# ProPrj_5V2A_2026-09-02.net
KiCad netlist of a schematic drawn in EasyEDA Pro
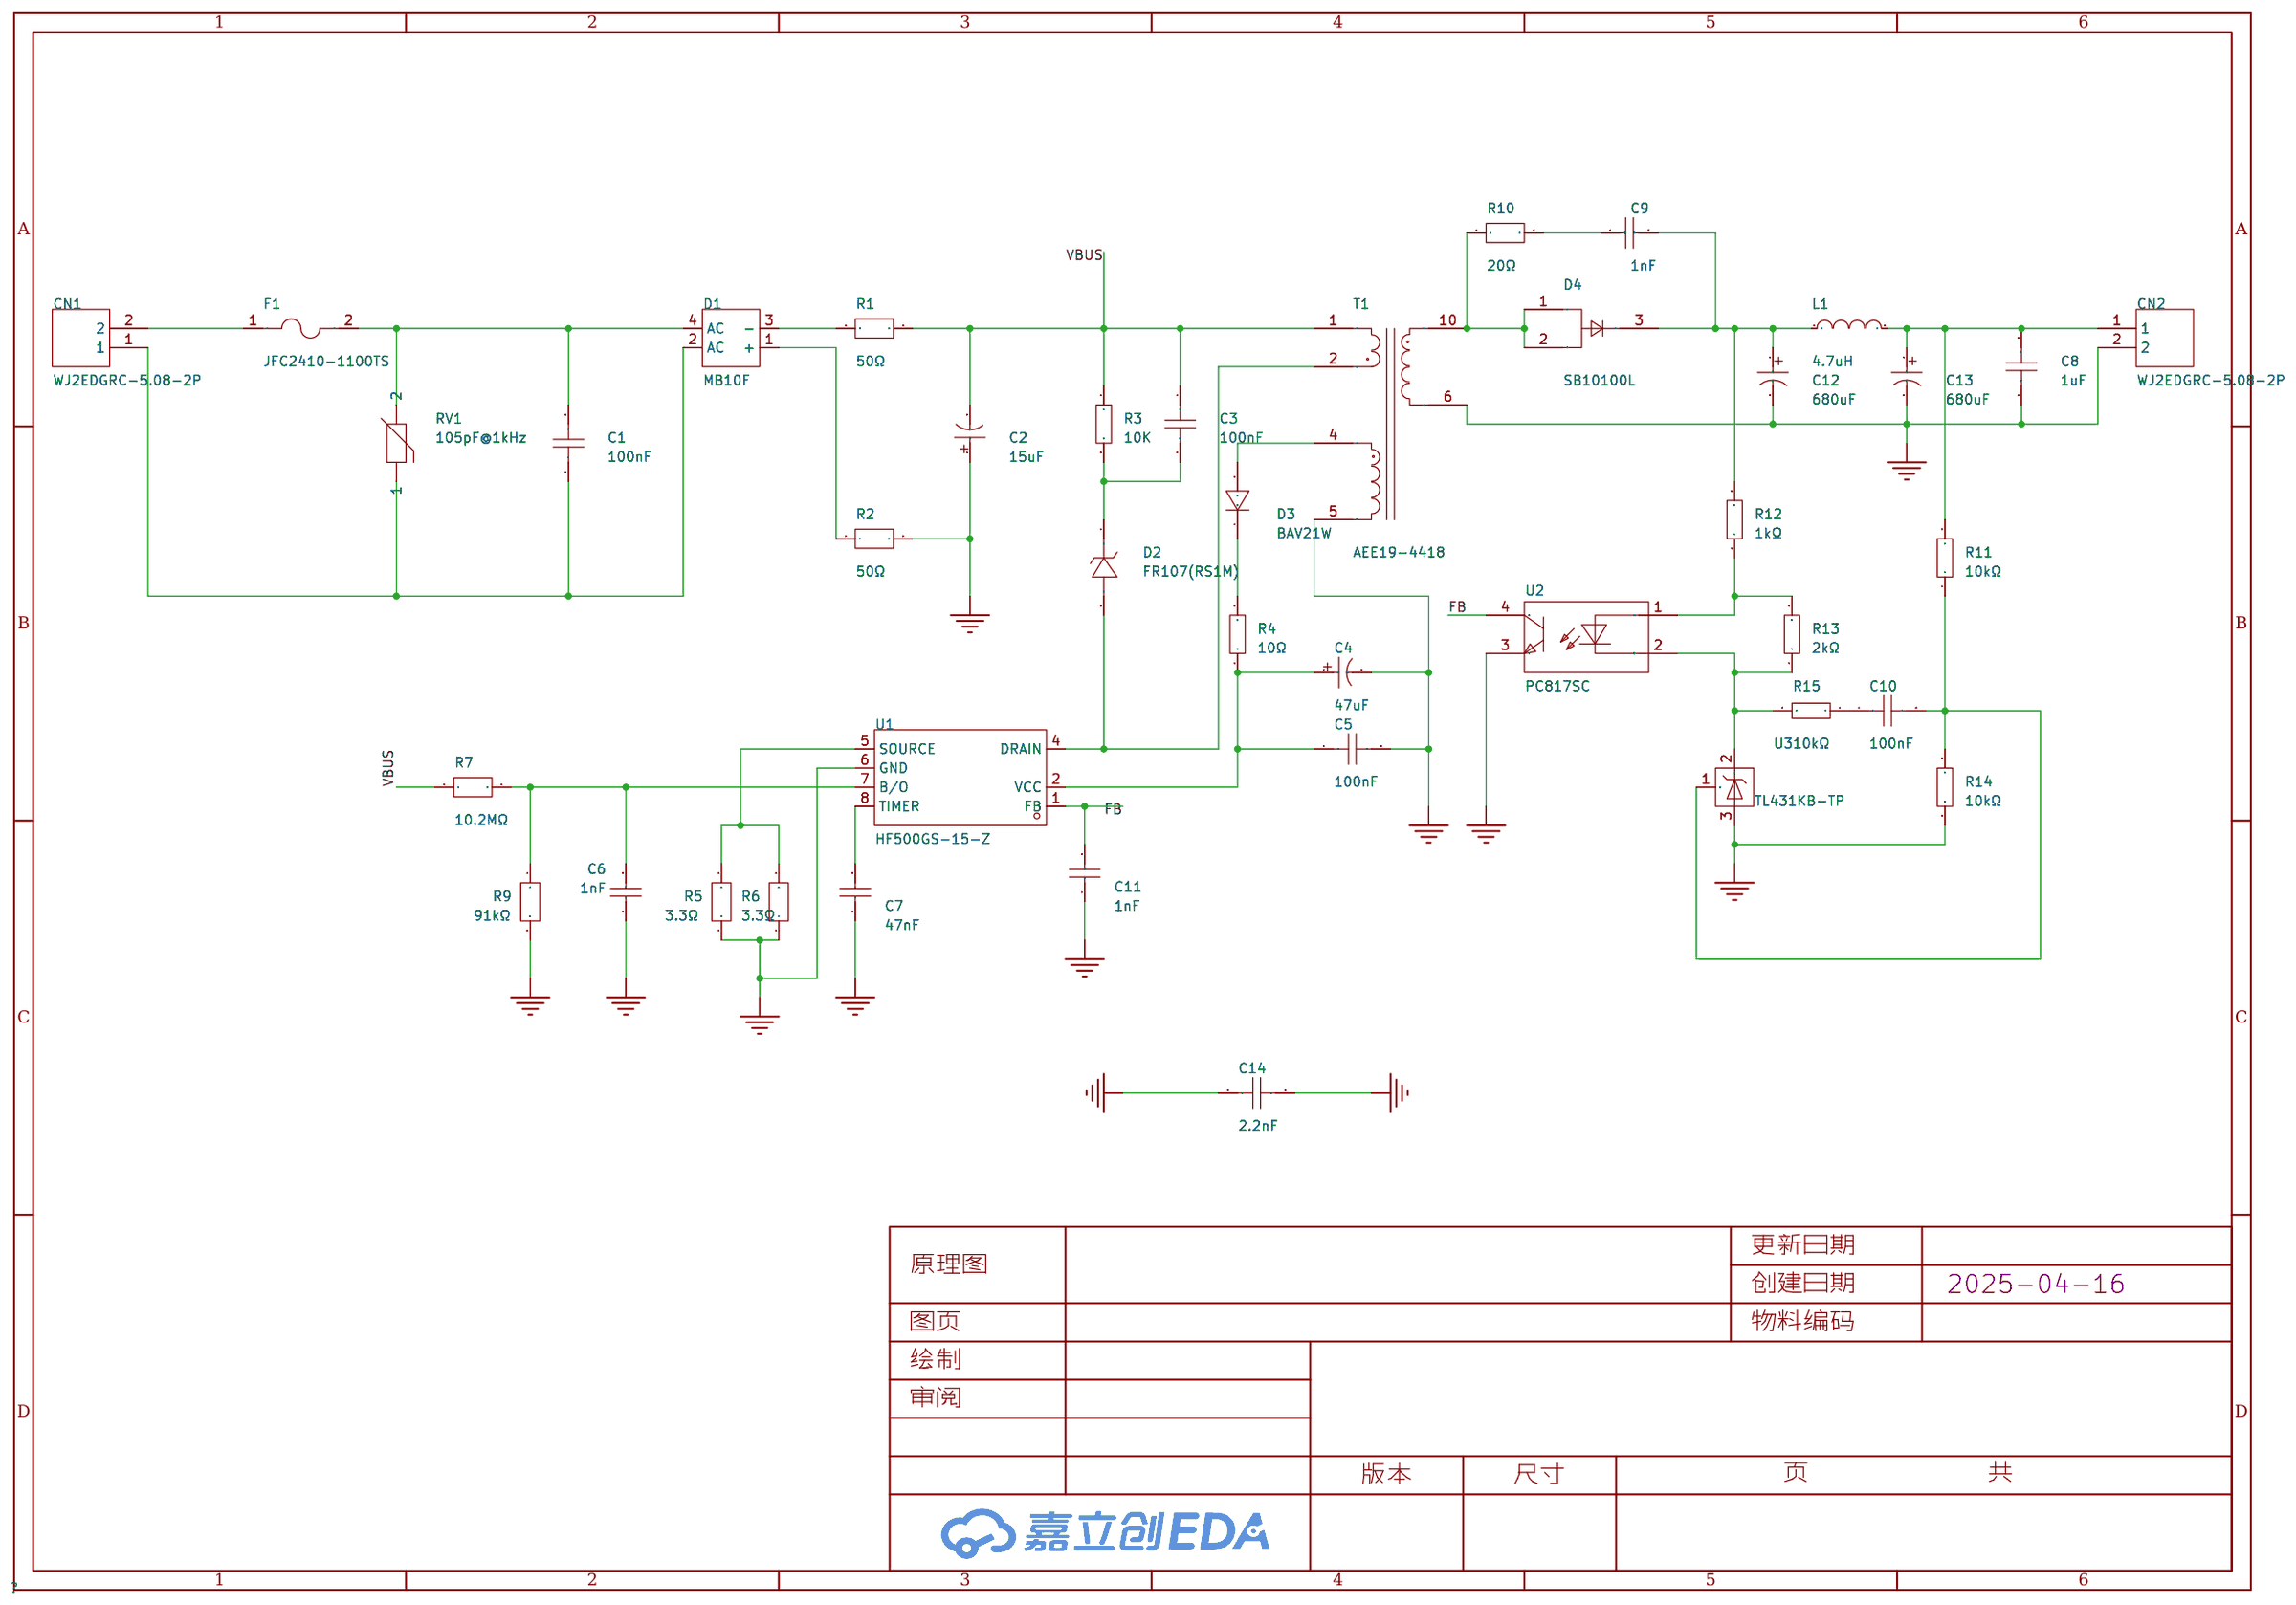
[diagram p0: schematic sheet]

(export (version "E")
  (design (tool "Eeschema 10.0.6"))
  (components
    (comp (ref "C1")
      (value "100nF")
      (footprint "easyedapro:CAP-TH_L13.0-W6.0-P10.00-D0.6")
      (description "容值:100nF;精度:±10%;工作电压(AC):275V；310V；305V;防护等级:X2;")
      (fields
        (field (name "Manufacturer Part") "MPX104K31C3KN15600")
        (field (name "Manufacturer") "KNSCHA(科尼盛)")
      )
      (libsource (lib "easyedapro") (part "MPX104K31C3KN15600"))
    )
    (comp (ref "C2")
      (value "15uF")
      (footprint "easyedapro:CAP-TH_BD10.0-P5.00-D1.0-FD")
      (description "容值:15uF;精度:±20%;额定电压:400V;纹波电流:-;等效串联电阻(ESR):-;")
      (fields
        (field (name "Manufacturer Part") "KM156M400G17RR0VH2FP0")
        (field (name "Manufacturer") "CX(承兴)")
      )
      (libsource (lib "easyedapro") (part "15UF/400V"))
    )
    (comp (ref "C3")
      (value "100nF")
      (footprint "easyedapro:C0603")
      (libsource (lib "easyedapro") (part "CapAcitance"))
    )
    (comp (ref "C4")
      (value "47uF")
      (footprint "easyedapro:CAP-TH_BD6.3-P2.50-D1.0-FD")
      (description "容值:47uF;精度:±20%;额定电压:50V;")
      (fields
        (field (name "Manufacturer Part") "KM476M050E11RR0VH2FP0")
        (field (name "Manufacturer") "CX(承兴)")
      )
      (libsource (lib "easyedapro") (part "47uF 50V 6.3*11_C45101"))
    )
    (comp (ref "C5")
      (value "100nF")
      (footprint "easyedapro:C0603")
      (description "容值:100nF;精度:±10%;额定电压:50V;温度系数:X7R;")
      (fields
        (field (name "Manufacturer Part") "CGA0603X7R104K500JT")
        (field (name "Manufacturer") "HRE(芯声)")
      )
      (libsource (lib "easyedapro") (part "CGA0603X7R104K500JT"))
    )
    (comp (ref "C6")
      (value "1nF")
      (footprint "easyedapro:C1206")
      (description "容值:1nF;精度:±10%;额定电压:2kV;温度系数:X7R;")
      (fields (field (name "Manufacturer Part") "1206B102K202NT") (field (name "Manufacturer") "FH(风华)"))
      (libsource (lib "easyedapro") (part "1206B102K202NT"))
    )
    (comp (ref "C7")
      (value "47nF")
      (footprint "easyedapro:C0603")
      (description "容值:47nF;精度:±10%;额定电压:50V;材质(温度系数):X7R;")
      (fields
        (field (name "Manufacturer Part") "CL10B473KB8NNNC")
        (field (name "Manufacturer") "SAMSUNG(三星)")
      )
      (libsource (lib "easyedapro") (part "CL10B473KB8NNNC"))
    )
    (comp (ref "C8")
      (value "1uF")
      (footprint "easyedapro:C0402")
      (description "容值:1uF;精度:±10%;额定电压:25V;材质(温度系数):X5R;")
      (fields
        (field (name "Manufacturer Part") "CL05A105KA5NQNC")
        (field (name "Manufacturer") "SAMSUNG(三星)")
      )
      (libsource (lib "easyedapro") (part "CL05A105KA5NQNC"))
    )
    (comp (ref "C9")
      (value "1nF")
      (footprint "easyedapro:C0603")
      (description "容值:1nF;精度:±10%;额定电压:50V;材质(温度系数):X7R;")
      (fields
        (field (name "Manufacturer Part") "CC0603KRX7R9BB102")
        (field (name "Manufacturer") "YAGEO(国巨)")
      )
      (libsource (lib "easyedapro") (part "CC0603KRX7R9BB102"))
    )
    (comp (ref "C10")
      (value "100nF")
      (footprint "easyedapro:C0603")
      (description "容值:100nF;精度:±10%;额定电压:50V;温度系数:X7R;")
      (fields
        (field (name "Manufacturer Part") "CGA0603X7R104K500JT")
        (field (name "Manufacturer") "HRE(芯声)")
      )
      (libsource (lib "easyedapro") (part "CGA0603X7R104K500JT"))
    )
    (comp (ref "C11")
      (value "1nF")
      (footprint "easyedapro:C0603")
      (description "容值:1nF;精度:±10%;额定电压:50V;材质(温度系数):X7R;")
      (fields
        (field (name "Manufacturer Part") "CL10B102KB8NNNC")
        (field (name "Manufacturer") "SAMSUNG(三星)")
      )
      (libsource (lib "easyedapro") (part "CL10B102KB8NNNC"))
    )
    (comp (ref "C12")
      (value "680uF")
      (footprint "easyedapro:CAP-TH_BD8.0-P3.50-D0.6-FD")
      (description "容值:680uF;精度:±20%;额定电压:16V;纹波电流:5.1A@100kHz;等效串联电阻(ESR):11mΩ@100kHz;类型:-;")
      (fields
        (field (name "Manufacturer Part") "ULR687M1CF1ARR")
        (field (name "Manufacturer") "MAN YUE(万裕科技)")
      )
      (libsource (lib "easyedapro") (part "ULR687M1CF1ARRX0CR"))
    )
    (comp (ref "C13")
      (value "680uF")
      (footprint "easyedapro:CAP-TH_BD8.0-P3.50-D0.6-FD")
      (description "容值:680uF;精度:±20%;额定电压:16V;纹波电流:5.1A@100kHz;等效串联电阻(ESR):11mΩ@100kHz;类型:-;")
      (fields
        (field (name "Manufacturer Part") "ULR687M1CF1ARR")
        (field (name "Manufacturer") "MAN YUE(万裕科技)")
      )
      (libsource (lib "easyedapro") (part "ULR687M1CF1ARRX0CR"))
    )
    (comp (ref "C14")
      (value "2.2nF")
      (footprint "easyedapro:CAP-TH_L10.0-W4.5-P10.00-D0.6-S4.0")
      (description "容值:2.2nF;精度:±20%;工作电压(AC):400V;防护等级:Y1;")
      (fields
        (field (name "Manufacturer Part") "AJTF222M2GF0200A082E")
        (field (name "Manufacturer") "KNSCHA(科尼盛)")
      )
      (libsource (lib "easyedapro") (part "AJTF222M2GF0200A082E"))
    )
    (comp (ref "CN1")
      (value "WJ2EDGRC-5.08-2P")
      (footprint "easyedapro:CONN-TH_2P-P5.08_WJ2EDGRC-5.08-2P")
      (fields (field (name "Manufacturer") "KANGNEX(康奈克斯电气)"))
      (libsource (lib "easyedapro") (part "WJ2EDGRC-5.08-2P"))
    )
    (comp (ref "CN2")
      (value "WJ2EDGRC-5.08-2P")
      (footprint "easyedapro:CONN-TH_2P-P5.08_WJ2EDGRC-5.08-2P")
      (fields (field (name "Manufacturer") "KANGNEX(康奈克斯电气)"))
      (libsource (lib "easyedapro") (part "WJ2EDGRC-5.08-2P"))
    )
    (comp (ref "D1")
      (value "MB10F")
      (footprint "easyedapro:MBF_L4.8-W3.9-P2.50-LS6.7-TR")
      (description "正向压降(Vf):1.1V@800mA;直流反向耐压(Vr):1kV;整流电流:800mA;正向浪涌电流(Ifsm):30A;")
      (fields (field (name "Manufacturer") "Hottech(合科泰)"))
      (libsource (lib "easyedapro") (part "MB10FH5G0NP"))
    )
    (comp (ref "D2")
      (value "FR107(RS1M)")
      (footprint "easyedapro:SMA_L4.3-W2.6-LS5.2-RD")
      (description "二极管配置:独立式;正向压降(Vf):1.3V@1A;直流反向耐压(Vr):1kV;整流电流:1A;反向恢复时间(trr):500ns;")
      (fields (field (name "Manufacturer") "KEXIN(科信)"))
      (libsource (lib "easyedapro") (part "FR107(RS1M)"))
    )
    (comp (ref "D3")
      (value "BAV21W")
      (footprint "easyedapro:SOD-123_L2.8-W1.8-LS3.7-RD")
      (description "二极管配置:独立式;正向压降(Vf):1.25V@200mA;直流反向耐压(Vr):200V;整流电流:200mA;反向恢复时间(trr):50ns;")
      (fields (field (name "Manufacturer") "CJ(江苏长电/长晶)"))
      (libsource (lib "easyedapro") (part "BAV21W"))
    )
    (comp (ref "D4")
      (value "SB10100L")
      (footprint "easyedapro:TO-277A_L4.7-W6.1-LS6.6-TR")
      (description "正向压降(Vf):850mV@10A;直流反向耐压(Vr):100V;整流电流:10A;")
      (fields (field (name "Manufacturer") "MDD(辰达半导体)"))
      (libsource (lib "easyedapro") (part "SB10100L"))
    )
    (comp (ref "F1")
      (value "JFC2410-1100TS")
      (footprint "easyedapro:F2410")
      (description "类型:贴片式保险丝;额定电流:1A;额定电压 (AC):250V;额定电压:250V;分断能力:50A;")
      (fields (field (name "Manufacturer") "JDTfuse(集电通)"))
      (libsource (lib "easyedapro") (part "JFC2410-1100TS"))
    )
    (comp (ref "L1")
      (value "4.7uH")
      (footprint "easyedapro:IND-SMD_L7.0-W6.6")
      (description "电感值:4.7uH;精度:±20%;额定电流:6A;饱和电流(Isat):9A;类型:一体成型电感;")
      (fields (field (name "Manufacturer Part") "FXL0630-4R7-M") (field (name "Manufacturer") "cjiang(长江微电)"))
      (libsource (lib "easyedapro") (part "FXL0630-4R7-M"))
    )
    (comp (ref "R1")
      (value "50Ω")
      (footprint "easyedapro:R1206")
      (description "电阻类型:薄膜电阻;阻值:50Ω;精度:±1%;功率:-;温度系数:±10ppm/°C;")
      (fields (field (name "Manufacturer Part") "AR06FTBV0500") (field (name "Manufacturer") "Viking(光颉)"))
      (libsource (lib "easyedapro") (part "AR06FTBV0500"))
    )
    (comp (ref "R2")
      (value "50Ω")
      (footprint "easyedapro:R1206")
      (description "电阻类型:薄膜电阻;阻值:50Ω;精度:±1%;功率:-;温度系数:±10ppm/°C;")
      (fields (field (name "Manufacturer Part") "AR06FTBV0500") (field (name "Manufacturer") "Viking(光颉)"))
      (libsource (lib "easyedapro") (part "AR06FTBV0500"))
    )
    (comp (ref "R3") (value "10K") (footprint "easyedapro:R0603") (libsource (lib "easyedapro") (part "电阻")))
    (comp (ref "R4")
      (value "10Ω")
      (footprint "easyedapro:R0603")
      (description "电阻类型:厚膜电阻;阻值:10Ω;精度:±1%;功率:100mW;最大工作电压:75V;温度系数:±400ppm/°C;")
      (fields
        (field (name "Manufacturer Part") "0603WAF100JT5E")
        (field (name "Manufacturer") "UNI-ROYAL(厚声)")
      )
      (libsource (lib "easyedapro") (part "0603WAF100JT5E"))
    )
    (comp (ref "R5")
      (value "3.3Ω")
      (footprint "easyedapro:R1206")
      (description "电阻类型:厚膜电阻;阻值:3.3Ω;精度:±1%;功率:250mW;最大工作电压:200V;温度系数:±200ppm/°C;")
      (fields (field (name "Manufacturer Part") "FRC1206F3R30TS") (field (name "Manufacturer") "FOJAN(富捷)"))
      (libsource (lib "easyedapro") (part "FRC1206F3R30TS"))
    )
    (comp (ref "R6")
      (value "3.3Ω")
      (footprint "easyedapro:R1206")
      (description "电阻类型:厚膜电阻;阻值:3.3Ω;精度:±1%;功率:250mW;最大工作电压:200V;温度系数:±200ppm/°C;")
      (fields (field (name "Manufacturer Part") "FRC1206F3R30TS") (field (name "Manufacturer") "FOJAN(富捷)"))
      (libsource (lib "easyedapro") (part "FRC1206F3R30TS"))
    )
    (comp (ref "R7")
      (value "10.2MΩ")
      (footprint "easyedapro:R1206")
      (description "电阻类型:厚膜电阻;阻值:10.2MΩ;精度:±1%;功率:250mW;最大工作电压:200V;温度系数:±100ppm/°C;")
      (fields
        (field (name "Manufacturer Part") "1206W4F1025T5E")
        (field (name "Manufacturer") "UNI-ROYAL(厚声)")
      )
      (libsource (lib "easyedapro") (part "1206W4F1025T5E"))
    )
    (comp (ref "R9")
      (value "91kΩ")
      (footprint "easyedapro:R0603")
      (description "电阻类型:厚膜电阻;阻值:91kΩ;精度:±1%;功率:100mW;工作电压:75V;温度系数:±100ppm/°C;")
      (fields (field (name "Manufacturer Part") "FRC0603F9102TS") (field (name "Manufacturer") "FOJAN(富捷)"))
      (libsource (lib "easyedapro") (part "FRC0603F9102TS"))
    )
    (comp (ref "R10")
      (value "20Ω")
      (footprint "easyedapro:R0603")
      (description "电阻类型:厚膜电阻;阻值:20Ω;精度:±1%;功率:100mW;工作电压:75V;温度系数:±100ppm/°C;")
      (fields (field (name "Manufacturer Part") "FRC0603F20R0TS") (field (name "Manufacturer") "FOJAN(富捷)"))
      (libsource (lib "easyedapro") (part "FRC0603F20R0TS"))
    )
    (comp (ref "R11")
      (value "10kΩ")
      (footprint "easyedapro:R0603")
      (description "电阻类型:厚膜电阻;阻值:10kΩ;精度:±1%;功率:100mW;最大工作电压:75V;温度系数:±100ppm/°C;")
      (fields
        (field (name "Manufacturer Part") "0603WAF1002T5E")
        (field (name "Manufacturer") "UNI-ROYAL(厚声)")
      )
      (libsource (lib "easyedapro") (part "0603WAF1002T5E"))
    )
    (comp (ref "R12")
      (value "1kΩ")
      (footprint "easyedapro:R0603")
      (description "电阻类型:厚膜电阻;阻值:1kΩ;精度:±1%;功率:100mW;最大工作电压:75V;温度系数:±100ppm/°C;")
      (fields
        (field (name "Manufacturer Part") "0603WAF1001T5E")
        (field (name "Manufacturer") "UNI-ROYAL(厚声)")
      )
      (libsource (lib "easyedapro") (part "0603WAF1001T5E"))
    )
    (comp (ref "R13")
      (value "2kΩ")
      (footprint "easyedapro:R0603")
      (description "电阻类型:厚膜电阻;阻值:2kΩ;精度:±1%;功率:100mW;最大工作电压:75V;温度系数:±100ppm/°C;")
      (fields
        (field (name "Manufacturer Part") "0603WAF2001T5E")
        (field (name "Manufacturer") "UNI-ROYAL(厚声)")
      )
      (libsource (lib "easyedapro") (part "0603WAF2001T5E"))
    )
    (comp (ref "R14")
      (value "10kΩ")
      (footprint "easyedapro:R0603")
      (description "电阻类型:厚膜电阻;阻值:10kΩ;精度:±1%;功率:100mW;最大工作电压:75V;温度系数:±100ppm/°C;")
      (fields
        (field (name "Manufacturer Part") "0603WAF1002T5E")
        (field (name "Manufacturer") "UNI-ROYAL(厚声)")
      )
      (libsource (lib "easyedapro") (part "0603WAF1002T5E"))
    )
    (comp (ref "R15")
      (value "10kΩ")
      (footprint "easyedapro:R0603")
      (description "电阻类型:厚膜电阻;阻值:10kΩ;精度:±1%;功率:100mW;最大工作电压:75V;温度系数:±100ppm/°C;")
      (fields
        (field (name "Manufacturer Part") "0603WAF1002T5E")
        (field (name "Manufacturer") "UNI-ROYAL(厚声)")
      )
      (libsource (lib "easyedapro") (part "0603WAF1002T5E"))
    )
    (comp (ref "RV1")
      (value "105pF@1kHz")
      (footprint "easyedapro:RES-TH_L9.0-W5.0-P6.00-D0.7-S3.00")
      (description "压敏电压:423V~517V;钳位电压:810V;工作电压:385V;工作电压(AC):300V;")
      (fields (field (name "Manufacturer Part") "07D471K") (field (name "Manufacturer") "COV(德欣)"))
      (libsource (lib "easyedapro") (part "07D471K_C317765"))
    )
    (comp (ref "T1")
      (value "AEE19-4418")
      (footprint "easyedapro:XFMR-TH_9P-L20.5-W16.9-P3.90-D0.7-S13.00_AEE19-4418")
      (description "初级电压:-;")
      (fields (field (name "Manufacturer") "Allied Components International"))
      (libsource (lib "easyedapro") (part "AEE19-4418"))
    )
    (comp (ref "U1")
      (value "HF500GS-15-Z")
      (footprint "easyedapro:SOIC-8_7P-L4.9-W3.9-P1.27-LS6.0-BL-PE3")
      (description "工作电压:12.5V~24V;开关频率:25kHz;晶体管耐压:700V;")
      (fields (field (name "Manufacturer") "MPS(芯源)"))
      (libsource (lib "easyedapro") (part "HF500GS-15-Z"))
    )
    (comp (ref "U2")
      (value "PC817SC")
      (footprint "easyedapro:SMD-4_L4.6-W6.5-P2.54-LS10.2-BL")
      (description "可替代C115502")
      (libsource (lib "easyedapro") (part "PC817S"))
    )
    (comp (ref "U3")
      (value "TL431KB-TP")
      (footprint "easyedapro:SOT-23-3_L2.9-W1.4-P1.91-LS2.6-BR")
      (description "输出类型:可编程;输入电压:-;输出电压:2.495V~36V;输出电流:100mA;精度:±0.4%;")
      (fields (field (name "Manufacturer") "MCC(美微科)"))
      (libsource (lib "easyedapro") (part "TL431KB-TP"))
    )
  )
  (nets
    (net (code "1") (name "/FB") (class "Default")
      (node (ref "C11") (pin "2") (pinfunction "2_2") (pintype "input"))
      (node (ref "U1") (pin "1") (pinfunction "FB_1") (pintype "unspecified"))
      (node (ref "U2") (pin "4") (pinfunction "COL_4") (pintype "unspecified"))
    )
    (net (code "2") (name "/VBUS") (class "Default")
      (node (ref "C2") (pin "2") (pinfunction "2_2") (pintype "input"))
      (node (ref "C3") (pin "1") (pinfunction "1_1") (pintype "input"))
      (node (ref "R1") (pin "2") (pinfunction "2_2") (pintype "unspecified"))
      (node (ref "R3") (pin "1") (pinfunction "1_1") (pintype "input"))
      (node (ref "R7") (pin "2") (pinfunction "2_2") (pintype "unspecified"))
      (node (ref "T1") (pin "1") (pinfunction "1_1") (pintype "unspecified"))
    )
    (net (code "3") (name "GND") (class "Default")
      (node (ref "C11") (pin "1") (pinfunction "1_1") (pintype "input"))
      (node (ref "C14") (pin "1") (pinfunction "1_1") (pintype "unspecified"))
      (node (ref "C2") (pin "1") (pinfunction "1_1") (pintype "input"))
      (node (ref "C4") (pin "2") (pinfunction "2_2") (pintype "input"))
      (node (ref "C5") (pin "2") (pinfunction "2_2") (pintype "unspecified"))
      (node (ref "C6") (pin "1") (pinfunction "1_1") (pintype "input"))
      (node (ref "C7") (pin "1") (pinfunction "1_1") (pintype "input"))
      (node (ref "R2") (pin "2") (pinfunction "2_2") (pintype "unspecified"))
      (node (ref "R5") (pin "1") (pinfunction "1_1") (pintype "unspecified"))
      (node (ref "R6") (pin "1") (pinfunction "1_1") (pintype "unspecified"))
      (node (ref "R9") (pin "2") (pinfunction "2_2") (pintype "unspecified"))
      (node (ref "T1") (pin "5") (pinfunction "5_5") (pintype "unspecified"))
      (node (ref "U1") (pin "6") (pinfunction "GND_6") (pintype "unspecified"))
      (node (ref "U2") (pin "3") (pinfunction "EM_3") (pintype "unspecified"))
    )
    (net (code "4") (name "GND1") (class "Default")
      (node (ref "C12") (pin "2") (pinfunction "2_2") (pintype "input"))
      (node (ref "C13") (pin "2") (pinfunction "2_2") (pintype "input"))
      (node (ref "C14") (pin "2") (pinfunction "2_2") (pintype "unspecified"))
      (node (ref "C8") (pin "1") (pinfunction "1_1") (pintype "unspecified"))
      (node (ref "CN2") (pin "2") (pinfunction "2_2") (pintype "unspecified"))
      (node (ref "R14") (pin "1") (pinfunction "1_1") (pintype "input"))
      (node (ref "T1") (pin "6") (pinfunction "6_6") (pintype "unspecified"))
      (node (ref "U3") (pin "3") (pinfunction "-_3") (pintype "unspecified"))
    )
    (net (code "5") (name "Net-(C1-Pad1)") (class "Default")
      (node (ref "C1") (pin "1") (pinfunction "1_1") (pintype "unspecified"))
      (node (ref "CN1") (pin "1") (pinfunction "1_1") (pintype "unspecified"))
      (node (ref "D1") (pin "2") (pinfunction "AC_2") (pintype "unspecified"))
      (node (ref "RV1") (pin "1") (pinfunction "1_1") (pintype "unspecified"))
    )
    (net (code "6") (name "Net-(C1-Pad2)") (class "Default")
      (node (ref "C1") (pin "2") (pinfunction "2_2") (pintype "unspecified"))
      (node (ref "D1") (pin "4") (pinfunction "AC_4") (pintype "unspecified"))
      (node (ref "F1") (pin "2") (pinfunction "2_2") (pintype "unspecified"))
      (node (ref "RV1") (pin "2") (pinfunction "2_2") (pintype "unspecified"))
    )
    (net (code "7") (name "Net-(C9-Pad1)") (class "Default")
      (node (ref "C9") (pin "1") (pinfunction "1_1") (pintype "input"))
      (node (ref "R10") (pin "2") (pinfunction "2_2") (pintype "unspecified"))
    )
    (net (code "8") (name "Net-(C10-Pad1)") (class "Default")
      (node (ref "C10") (pin "1") (pinfunction "1_1") (pintype "unspecified"))
      (node (ref "R15") (pin "1") (pinfunction "1_1") (pintype "input"))
    )
    (net (code "9") (name "Net-(C12-Pad1)") (class "Default")
      (node (ref "C12") (pin "1") (pinfunction "1_1") (pintype "input"))
      (node (ref "C9") (pin "2") (pinfunction "2_2") (pintype "input"))
      (node (ref "D4") (pin "3") (pinfunction "3_3") (pintype "unspecified"))
      (node (ref "L1") (pin "1") (pinfunction "1_1") (pintype "unspecified"))
      (node (ref "R12") (pin "2") (pinfunction "2_2") (pintype "input"))
    )
    (net (code "10") (name "Net-(C13-Pad1)") (class "Default")
      (node (ref "C13") (pin "1") (pinfunction "1_1") (pintype "input"))
      (node (ref "C8") (pin "2") (pinfunction "2_2") (pintype "unspecified"))
      (node (ref "CN2") (pin "1") (pinfunction "1_1") (pintype "unspecified"))
      (node (ref "L1") (pin "2") (pinfunction "2_2") (pintype "unspecified"))
      (node (ref "R11") (pin "2") (pinfunction "2_2") (pintype "input"))
    )
    (net (code "11") (name "Net-(CN1-Pad2)") (class "Default")
      (node (ref "CN1") (pin "2") (pinfunction "2_2") (pintype "unspecified"))
      (node (ref "F1") (pin "1") (pinfunction "1_1") (pintype "unspecified"))
    )
    (net (code "12") (name "Net-(D1-+)") (class "Default")
      (node (ref "D1") (pin "1") (pinfunction "+_1") (pintype "unspecified"))
      (node (ref "R2") (pin "1") (pinfunction "1_1") (pintype "unspecified"))
    )
    (net (code "13") (name "Net-(D1--)") (class "Default")
      (node (ref "D1") (pin "3") (pinfunction "-_3") (pintype "unspecified"))
      (node (ref "R1") (pin "1") (pinfunction "1_1") (pintype "unspecified"))
    )
    (net (code "14") (name "Net-(D2-A)") (class "Default")
      (node (ref "D2") (pin "2") (pinfunction "A_2") (pintype "unspecified"))
      (node (ref "T1") (pin "2") (pinfunction "2_2") (pintype "unspecified"))
      (node (ref "U1") (pin "4") (pinfunction "DRAIN_4") (pintype "unspecified"))
    )
    (net (code "15") (name "Net-(D2-C)") (class "Default")
      (node (ref "C3") (pin "2") (pinfunction "2_2") (pintype "input"))
      (node (ref "D2") (pin "1") (pinfunction "C_1") (pintype "unspecified"))
      (node (ref "R3") (pin "2") (pinfunction "2_2") (pintype "input"))
    )
    (net (code "16") (name "Net-(D3-A)") (class "Default")
      (node (ref "D3") (pin "2") (pinfunction "A_2") (pintype "unspecified"))
      (node (ref "T1") (pin "4") (pinfunction "4_4") (pintype "unspecified"))
    )
    (net (code "17") (name "Net-(D3-C)") (class "Default")
      (node (ref "D3") (pin "1") (pinfunction "C_1") (pintype "unspecified"))
      (node (ref "R4") (pin "2") (pinfunction "2_2") (pintype "input"))
    )
    (net (code "18") (name "Net-(D4-Pad1)") (class "Default")
      (node (ref "D4") (pin "1") (pinfunction "1_1") (pintype "unspecified"))
      (node (ref "D4") (pin "2") (pinfunction "2_2") (pintype "unspecified"))
      (node (ref "R10") (pin "1") (pinfunction "1_1") (pintype "unspecified"))
      (node (ref "T1") (pin "10") (pinfunction "10_10") (pintype "unspecified"))
    )
    (net (code "19") (name "Net-(U1-B{slash}O)") (class "Default")
      (node (ref "C6") (pin "2") (pinfunction "2_2") (pintype "input"))
      (node (ref "R7") (pin "1") (pinfunction "1_1") (pintype "unspecified"))
      (node (ref "R9") (pin "1") (pinfunction "1_1") (pintype "unspecified"))
      (node (ref "U1") (pin "7") (pinfunction "B/O_7") (pintype "unspecified"))
    )
    (net (code "20") (name "Net-(U1-SOURCE)") (class "Default")
      (node (ref "R5") (pin "2") (pinfunction "2_2") (pintype "unspecified"))
      (node (ref "R6") (pin "2") (pinfunction "2_2") (pintype "unspecified"))
      (node (ref "U1") (pin "5") (pinfunction "SOURCE_5") (pintype "unspecified"))
    )
    (net (code "21") (name "Net-(U1-TIMER)") (class "Default")
      (node (ref "C7") (pin "2") (pinfunction "2_2") (pintype "input"))
      (node (ref "U1") (pin "8") (pinfunction "TIMER_8") (pintype "unspecified"))
    )
    (net (code "22") (name "Net-(U1-VCC)") (class "Default")
      (node (ref "C4") (pin "1") (pinfunction "1_1") (pintype "input"))
      (node (ref "C5") (pin "1") (pinfunction "1_1") (pintype "unspecified"))
      (node (ref "R4") (pin "1") (pinfunction "1_1") (pintype "input"))
      (node (ref "U1") (pin "2") (pinfunction "VCC_2") (pintype "unspecified"))
    )
    (net (code "23") (name "Net-(U2-AN)") (class "Default")
      (node (ref "R12") (pin "1") (pinfunction "1_1") (pintype "input"))
      (node (ref "R13") (pin "2") (pinfunction "2_2") (pintype "input"))
      (node (ref "U2") (pin "1") (pinfunction "AN_1") (pintype "unspecified"))
    )
    (net (code "24") (name "Net-(U2-CAT)") (class "Default")
      (node (ref "R13") (pin "1") (pinfunction "1_1") (pintype "input"))
      (node (ref "R15") (pin "2") (pinfunction "2_2") (pintype "input"))
      (node (ref "U2") (pin "2") (pinfunction "CAT_2") (pintype "unspecified"))
      (node (ref "U3") (pin "2") (pinfunction "+_2") (pintype "unspecified"))
    )
    (net (code "25") (name "Net-(U3-REF)") (class "Default")
      (node (ref "C10") (pin "2") (pinfunction "2_2") (pintype "unspecified"))
      (node (ref "R11") (pin "1") (pinfunction "1_1") (pintype "input"))
      (node (ref "R14") (pin "2") (pinfunction "2_2") (pintype "input"))
      (node (ref "U3") (pin "1") (pinfunction "REF_1") (pintype "unspecified"))
    )
  )
)
